# SoftPowerSwitch.net
KiCad netlist of a schematic drawn in Altium Designer
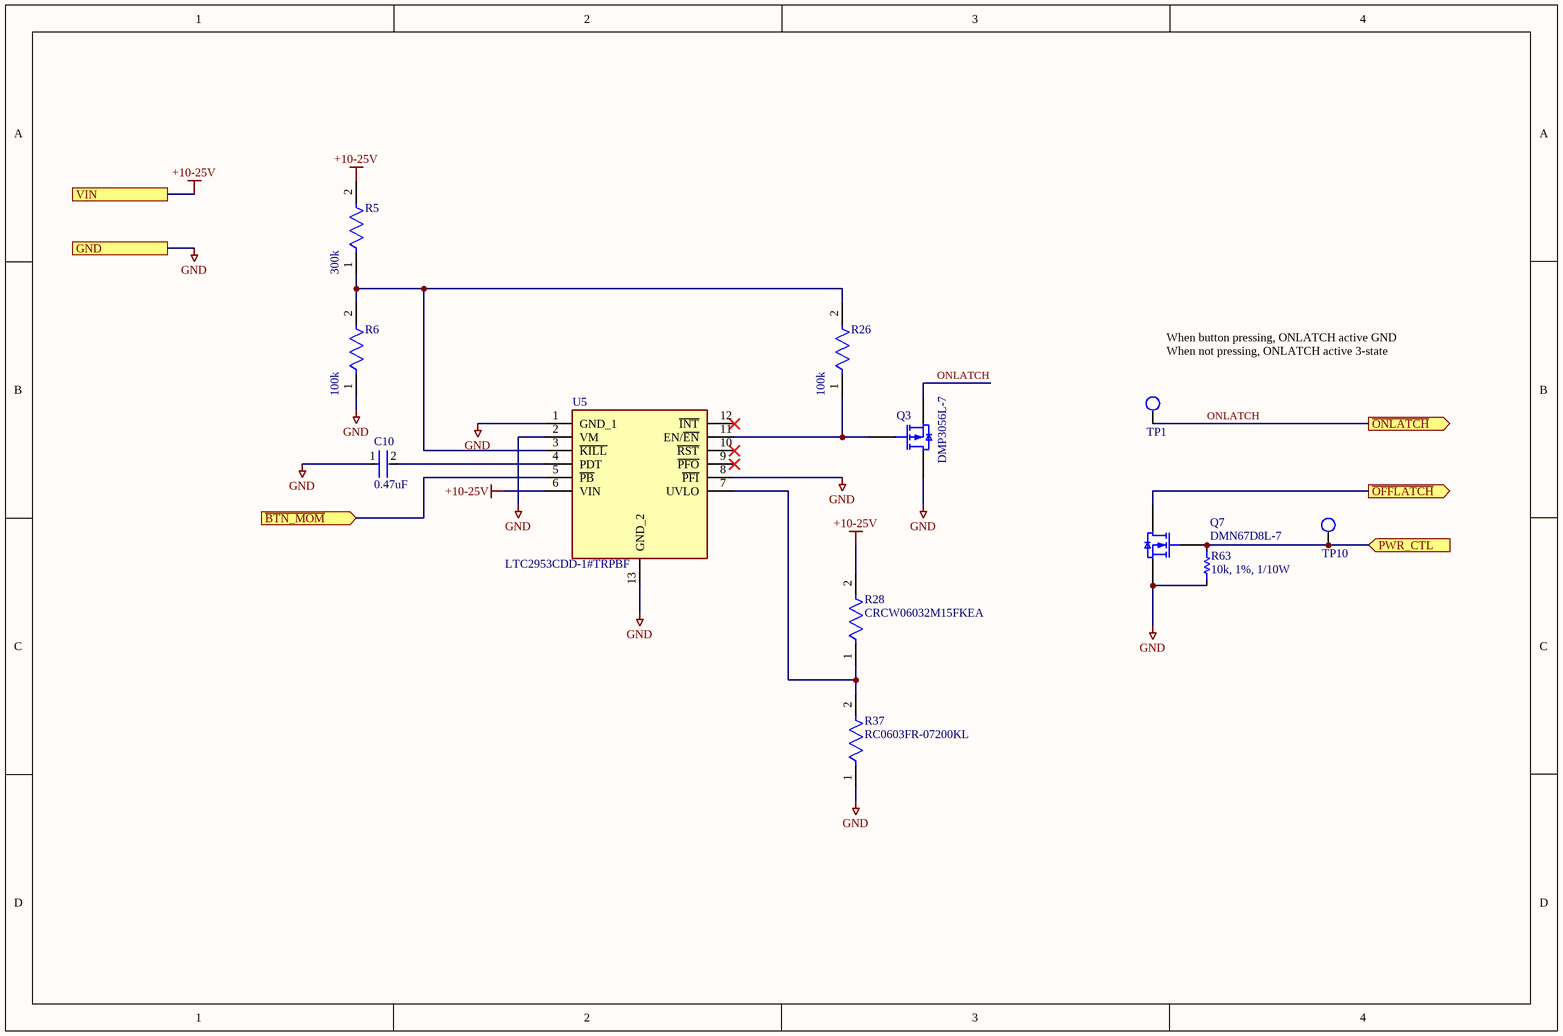
[diagram p0: SoftPowerSwitch.SchDoc]

(export (version "E")
  (design (tool "Eeschema 10.0.6"))
  (components
    (comp (ref "C10")
      (value "0.47uF")
      (footprint "FP-C0603C-CF-MFG")
      (description "CAP CER 0.47UF 16V 10% X5R 0603")
      (fields
        (field (name "MANUFACTURER PART NUMBER") "C0603C474K4PACTU")
        (field (name "MANUFACTURER") "KEMET")
      )
      (libsource (lib "Altium Content Vault") (part "b4654b650e69147ec39a6b967a45e02"))
    )
    (comp (ref "Q3")
      (value "DMP3056L-7")
      (footprint "SOT23-3")
      (description "MOSFET P-CH 30V 4.3A SOT23")
      (fields (field (name "PART NUMBER") "NS00910"))
      (libsource (lib "FullPartsDB") (part "FET_P_GSD"))
    )
    (comp (ref "Q7")
      (value "DMN67D8L-7")
      (footprint "SOT23-3")
      (description "MOSFET N-CH 60V 210MA SOT23")
      (fields (field (name "PART NUMBER") "NS00873") (field (name "PUBLISHER") "Altium Limited"))
      (libsource (lib "FullPartsDB") (part "FET_N_GSD"))
    )
    (comp (ref "R5")
      (value "300k")
      (footprint "FP-ERA3A-IPC_C")
      (description "RES SMD 300K OHM 0.1% 1/10W 0603")
      (fields (field (name "TOLERANCE") "0.1%"))
      (libsource (lib "Altium Content Vault") (part "1029c3af85768c4190bb7ad29bc67b5"))
    )
    (comp (ref "R6")
      (value "100k")
      (footprint "FP-RC0603-0_55-MFG")
      (description "RES SMD 100K OHM 1% 1/10W 0603")
      (fields (field (name "TOLERANCE") "1%"))
      (libsource (lib "Altium Content Vault") (part "1029c3af85768c4190bb7ad29bc67b5"))
    )
    (comp (ref "R26")
      (value "100k")
      (footprint "FP-RC0603-0_55-MFG")
      (description "RES SMD 100K OHM 1% 1/10W 0603")
      (fields (field (name "TOLERANCE") "1%"))
      (libsource (lib "Altium Content Vault") (part "1029c3af85768c4190bb7ad29bc67b5"))
    )
    (comp (ref "R28")
      (value "CRCW06032M15FKEA")
      (footprint "FP-CRCW0603-e3-IPC_A")
      (description "RES Thick Film, 2.15MΩ, 1%, 0.1W, 100ppm/°C, 0603")
      (fields (field (name "TOLERANCE") "1%"))
      (libsource (lib "Altium Content Vault") (part "1029c3af85768c4190bb7ad29bc67b5"))
    )
    (comp (ref "R37")
      (value "RC0603FR-07200KL")
      (footprint "FP-RC0603-0_55-IPC_B")
      (description "RES SMD 200K OHM 1% 1/10W 0603")
      (fields (field (name "TOLERANCE") "1%"))
      (libsource (lib "Altium Content Vault") (part "1029c3af85768c4190bb7ad29bc67b5"))
    )
    (comp (ref "R63")
      (value "10k, 1%, 1/10W")
      (footprint "0603")
      (description "RES 10K OHM 1% 1/10W 0603")
      (fields (field (name "PART NUMBER") "NS00820"))
      (libsource (lib "FullPartsDB") (part "RESISTOR"))
    )
    (comp (ref "TP1")
      (value "2mm")
      (footprint "TEST POINT 40 Mil")
      (description "Testpoint 2mm round")
      (fields (field (name "PART NUMBER") "NS00254"))
      (libsource (lib "FullPartsDB") (part "TESTPOINT"))
    )
    (comp (ref "TP10")
      (value "2mm")
      (footprint "TEST POINT 40 Mil")
      (description "Testpoint 2mm round")
      (fields (field (name "PART NUMBER") "NS00254"))
      (libsource (lib "FullPartsDB") (part "TESTPOINT"))
    )
    (comp (ref "U5")
      (value "LTC2953CDD-1#TRPBF")
      (footprint "SamacSys:SON45P300X300X80-13N-D")
      (description "Integrated Circuit")
      (fields
        (field (name "MANUFACTURER_PART_NUMBER") "LTC2953CDD-1#PBF")
        (field (name "MOUSER PART NUMBER") "584-LTC2953CDD-1#PBF")
      )
      (libsource (lib "*") (part "LTC2953CDD-1#PBF"))
    )
  )
  (nets
    (net (code "1") (name "+10-25V") (class "Default")
      (node (ref "R28") (pin "2") (pinfunction "2_2") (pintype "passive"))
      (node (ref "R5") (pin "2") (pinfunction "2_2") (pintype "passive"))
      (node (ref "U5") (pin "6") (pinfunction "VIN_6") (pintype "passive"))
    )
    (net (code "2") (name "/BTN_MOM") (class "Default")
      (node (ref "U5") (pin "5") (pinfunction "~{PB}_5") (pintype "passive"))
    )
    (net (code "3") (name "/OFFLATCH") (class "Default")
      (node (ref "Q7") (pin "3") (pinfunction "D_3") (pintype "passive"))
    )
    (net (code "4") (name "/ONLATCH") (class "Default")
      (node (ref "Q3") (pin "2") (pinfunction "S_2") (pintype "passive"))
      (node (ref "TP1") (pin "1") (pinfunction "TP_1") (pintype "passive"))
    )
    (net (code "5") (name "/PWR_CTL") (class "Default")
      (node (ref "Q7") (pin "1") (pinfunction "G_1") (pintype "passive"))
      (node (ref "R63") (pin "2") (pinfunction "2_2") (pintype "passive"))
      (node (ref "TP10") (pin "1") (pinfunction "TP_1") (pintype "passive"))
    )
    (net (code "6") (name "GND") (class "Default")
      (node (ref "C10") (pin "1") (pinfunction "1_1") (pintype "passive"))
      (node (ref "Q3") (pin "3") (pinfunction "D_3") (pintype "passive"))
      (node (ref "Q7") (pin "2") (pinfunction "S_2") (pintype "passive"))
      (node (ref "R37") (pin "1") (pinfunction "1_1") (pintype "passive"))
      (node (ref "R6") (pin "1") (pinfunction "1_1") (pintype "passive"))
      (node (ref "R63") (pin "1") (pinfunction "1_1") (pintype "passive"))
      (node (ref "U5") (pin "1") (pinfunction "GND_1_1") (pintype "passive"))
      (node (ref "U5") (pin "13") (pinfunction "GND_2_13") (pintype "passive"))
      (node (ref "U5") (pin "2") (pinfunction "VM_2") (pintype "passive"))
      (node (ref "U5") (pin "8") (pinfunction "~{PFI}_8") (pintype "passive"))
    )
    (net (code "7") (name "Net-(Q3-G)") (class "Default")
      (node (ref "Q3") (pin "1") (pinfunction "G_1") (pintype "passive"))
      (node (ref "R26") (pin "1") (pinfunction "1_1") (pintype "passive"))
      (node (ref "U5") (pin "11") (pinfunction "EN/~{EN}_11") (pintype "passive"))
    )
    (net (code "8") (name "Net-(U5-PDT)") (class "Default")
      (node (ref "C10") (pin "2") (pinfunction "2_2") (pintype "passive"))
      (node (ref "U5") (pin "4") (pinfunction "PDT_4") (pintype "passive"))
    )
    (net (code "9") (name "Net-(U5-UVLO)") (class "Default")
      (node (ref "R28") (pin "1") (pinfunction "1_1") (pintype "passive"))
      (node (ref "R37") (pin "2") (pinfunction "2_2") (pintype "passive"))
      (node (ref "U5") (pin "7") (pinfunction "UVLO_7") (pintype "passive"))
    )
    (net (code "10") (name "Net-(U5-~{KILL})") (class "Default")
      (node (ref "R26") (pin "2") (pinfunction "2_2") (pintype "passive"))
      (node (ref "R5") (pin "1") (pinfunction "1_1") (pintype "passive"))
      (node (ref "R6") (pin "2") (pinfunction "2_2") (pintype "passive"))
      (node (ref "U5") (pin "3") (pinfunction "~{KILL}_3") (pintype "passive"))
    )
    (net (code "11") (name "unconnected-(U5-~{INT}-Pad12)") (class "Default")
      (node (ref "U5") (pin "12") (pinfunction "~{INT}_12") (pintype "passive+no_connect"))
    )
    (net (code "12") (name "unconnected-(U5-~{PFO}-Pad9)") (class "Default")
      (node (ref "U5") (pin "9") (pinfunction "~{PFO}_9") (pintype "passive+no_connect"))
    )
    (net (code "13") (name "unconnected-(U5-~{RST}-Pad10)") (class "Default")
      (node (ref "U5") (pin "10") (pinfunction "~{RST}_10") (pintype "passive+no_connect"))
    )
  )
)
